# BJ_GIRA_Taster4_4.net
KiCad netlist of a schematic drawn in EAGLE
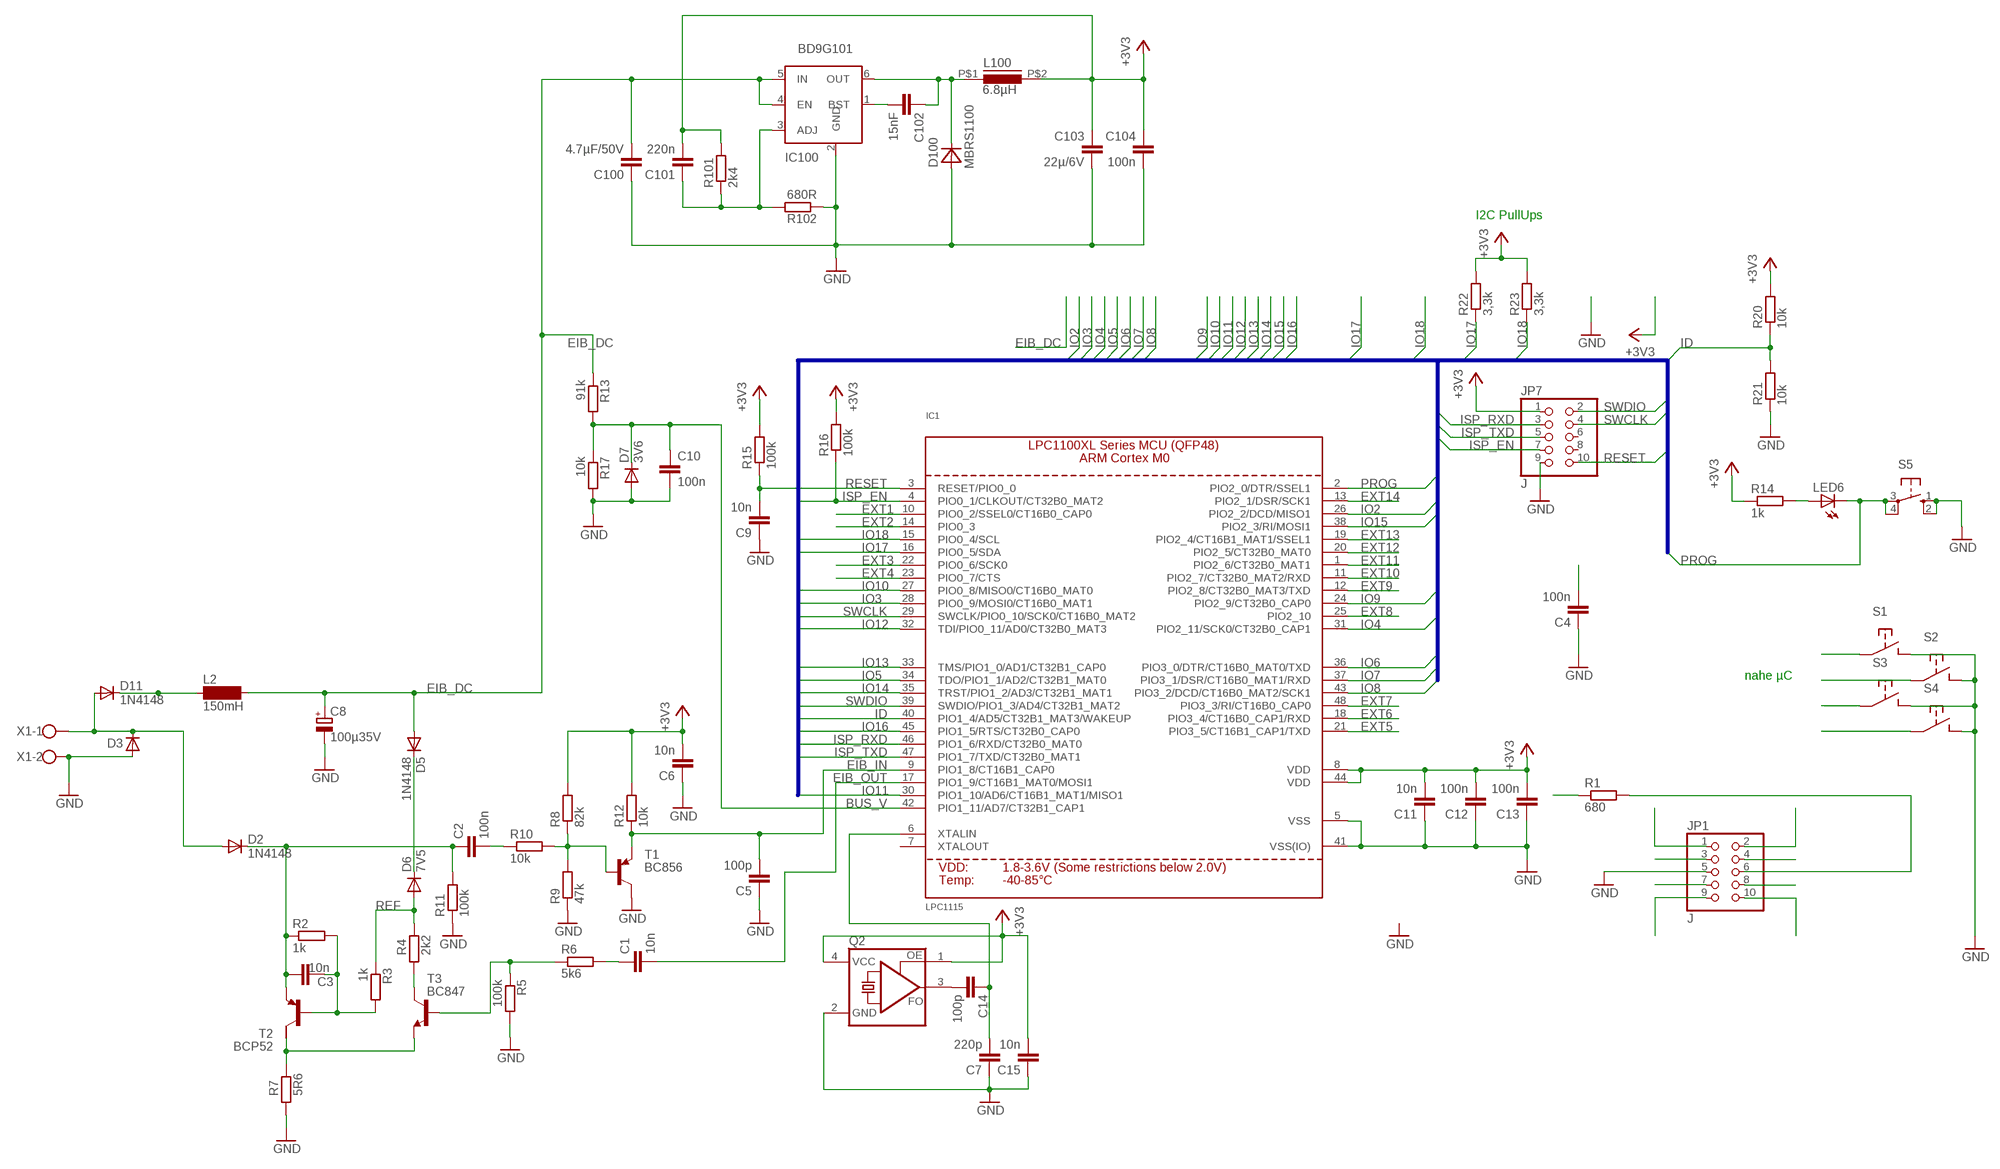
[diagram p0: schematic, sheet 1]

(export (version "E")
  (design (tool "Eeschema 10.0.6"))
  (components
    (comp (ref "C1")
      (value "10n")
      (footprint "eagle-import:C1206")
      (libsource (lib "eagle-import") (part "C-EUC1206"))
    )
    (comp (ref "C2")
      (value "100n")
      (footprint "eagle-import:C1206")
      (libsource (lib "eagle-import") (part "C-EUC1206"))
    )
    (comp (ref "C3")
      (value "10n")
      (footprint "eagle-import:C1206")
      (libsource (lib "eagle-import") (part "C-EUC1206"))
    )
    (comp (ref "C4")
      (value "100n")
      (footprint "eagle-import:C1206")
      (libsource (lib "eagle-import") (part "C-EUC1206"))
    )
    (comp (ref "C5")
      (value "100p")
      (footprint "eagle-import:C1206")
      (libsource (lib "eagle-import") (part "C-EUC1206"))
    )
    (comp (ref "C6")
      (value "10n")
      (footprint "eagle-import:C1206")
      (libsource (lib "eagle-import") (part "C-EUC1206"))
    )
    (comp (ref "C7")
      (value "220p")
      (footprint "eagle-import:C1206")
      (libsource (lib "eagle-import") (part "C-EUC1206"))
    )
    (comp (ref "C8")
      (value "100µ35V")
      (footprint "eagle-import:E3,5-8")
      (libsource (lib "eagle-import") (part "CPOL-EUE3.5-8"))
    )
    (comp (ref "C9")
      (value "10n")
      (footprint "eagle-import:C1206")
      (libsource (lib "eagle-import") (part "C-EUC1206"))
    )
    (comp (ref "C10")
      (value "100n")
      (footprint "eagle-import:C1206")
      (libsource (lib "eagle-import") (part "C-EUC1206"))
    )
    (comp (ref "C11")
      (value "10n")
      (footprint "eagle-import:C1206")
      (libsource (lib "eagle-import") (part "C-EUC1206"))
    )
    (comp (ref "C12")
      (value "100n")
      (footprint "eagle-import:C1206")
      (libsource (lib "eagle-import") (part "C-EUC1206"))
    )
    (comp (ref "C13")
      (value "100n")
      (footprint "eagle-import:C1206")
      (libsource (lib "eagle-import") (part "C-EUC1206"))
    )
    (comp (ref "C14")
      (value "100p")
      (footprint "eagle-import:C1206")
      (libsource (lib "eagle-import") (part "C-EUC1206"))
    )
    (comp (ref "C15")
      (value "10n")
      (footprint "eagle-import:C1206")
      (libsource (lib "eagle-import") (part "C-EUC1206"))
    )
    (comp (ref "C100")
      (value "4.7µF/50V")
      (footprint "eagle-import:C1206")
      (libsource (lib "eagle-import") (part "C-EUC1206"))
    )
    (comp (ref "C101")
      (value "220n")
      (footprint "eagle-import:C1206")
      (libsource (lib "eagle-import") (part "C-EUC1206"))
    )
    (comp (ref "C102")
      (value "15nF")
      (footprint "eagle-import:C1206")
      (libsource (lib "eagle-import") (part "C-EUC1206"))
    )
    (comp (ref "C103")
      (value "22µ/6V")
      (footprint "eagle-import:C1206")
      (libsource (lib "eagle-import") (part "C-EUC1206"))
    )
    (comp (ref "C104")
      (value "100n")
      (footprint "eagle-import:C1206")
      (libsource (lib "eagle-import") (part "C-EUC1206"))
    )
    (comp (ref "D2")
      (value "1N4148")
      (footprint "eagle-import:MINIMELF")
      (libsource (lib "eagle-import") (part "DIODE-MINIMELF"))
    )
    (comp (ref "D3")
      (value "D-SMB")
      (footprint "eagle-import:SMB")
      (libsource (lib "eagle-import") (part "D-SMB"))
    )
    (comp (ref "D5")
      (value "1N4148")
      (footprint "eagle-import:MINIMELF")
      (libsource (lib "eagle-import") (part "DIODE-MINIMELF"))
    )
    (comp (ref "D6")
      (value "7V5")
      (footprint "eagle-import:MINIMELF")
      (libsource (lib "eagle-import") (part "DIODE-MINIMELF"))
    )
    (comp (ref "D7")
      (value "3V6")
      (footprint "eagle-import:MINIMELF")
      (libsource (lib "eagle-import") (part "DIODE-MINIMELF"))
    )
    (comp (ref "D11")
      (value "1N4148")
      (footprint "eagle-import:MINIMELF")
      (libsource (lib "eagle-import") (part "DIODE-MINIMELF"))
    )
    (comp (ref "D100")
      (value "MBRS1100")
      (footprint "eagle-import:SMA")
      (libsource (lib "eagle-import") (part "MBRA340T3"))
    )
    (comp (ref "IC1")
      (value "LPC1115")
      (footprint "eagle-import:LQFP48")
      (libsource (lib "eagle-import") (part "LPC1113/4/5_QFP48_XLSERIES"))
    )
    (comp (ref "IC100")
      (value "BD9G101")
      (footprint "eagle-import:SOT23-6")
      (libsource (lib "eagle-import") (part "BD9G101GBD9G101G-SOT23-6"))
    )
    (comp (ref "JP1")
      (value "J")
      (footprint "eagle-import:2X05M")
      (libsource (lib "eagle-import") (part "PINHD-2X05_2.00"))
    )
    (comp (ref "JP7")
      (value "J")
      (footprint "eagle-import:2X05M")
      (libsource (lib "eagle-import") (part "PINHD-2X05_2.00"))
    )
    (comp (ref "L2")
      (value "150mH")
      (footprint "eagle-import:BS11")
      (libsource (lib "eagle-import") (part "BS11"))
    )
    (comp (ref "L100")
      (value "6.8µH")
      (footprint "eagle-import:PIS2812")
      (libsource (lib "eagle-import") (part "IND_FASTRON_1616FPS"))
    )
    (comp (ref "LED6")
      (value "LED3MM")
      (footprint "eagle-import:LED3MM")
      (libsource (lib "eagle-import") (part "LED3MM"))
    )
    (comp (ref "Q2")
      (value "ASFL")
      (footprint "eagle-import:ASF")
      (libsource (lib "eagle-import") (part "ASFL"))
    )
    (comp (ref "R1")
      (value "680")
      (footprint "eagle-import:R1206")
      (libsource (lib "eagle-import") (part "R-EU_R1206"))
    )
    (comp (ref "R2")
      (value "1k")
      (footprint "eagle-import:R1206")
      (libsource (lib "eagle-import") (part "R-EU_R1206"))
    )
    (comp (ref "R3")
      (value "1k")
      (footprint "eagle-import:R1206")
      (libsource (lib "eagle-import") (part "R-EU_R1206"))
    )
    (comp (ref "R4")
      (value "2k2")
      (footprint "eagle-import:R1206")
      (libsource (lib "eagle-import") (part "R-EU_R1206"))
    )
    (comp (ref "R5")
      (value "100k")
      (footprint "eagle-import:R1206")
      (libsource (lib "eagle-import") (part "R-EU_R1206"))
    )
    (comp (ref "R6")
      (value "5k6")
      (footprint "eagle-import:R1206")
      (libsource (lib "eagle-import") (part "R-EU_R1206"))
    )
    (comp (ref "R7")
      (value "5R6")
      (footprint "eagle-import:R1206")
      (libsource (lib "eagle-import") (part "R-EU_R1206"))
    )
    (comp (ref "R8")
      (value "82k")
      (footprint "eagle-import:R1206")
      (libsource (lib "eagle-import") (part "R-EU_R1206"))
    )
    (comp (ref "R9")
      (value "47k")
      (footprint "eagle-import:R1206")
      (libsource (lib "eagle-import") (part "R-EU_R1206"))
    )
    (comp (ref "R10")
      (value "10k")
      (footprint "eagle-import:R1206")
      (libsource (lib "eagle-import") (part "R-EU_R1206"))
    )
    (comp (ref "R11")
      (value "100k")
      (footprint "eagle-import:R1206")
      (libsource (lib "eagle-import") (part "R-EU_R1206"))
    )
    (comp (ref "R12")
      (value "10k")
      (footprint "eagle-import:R1206")
      (libsource (lib "eagle-import") (part "R-EU_R1206"))
    )
    (comp (ref "R13")
      (value "91k")
      (footprint "eagle-import:R1206")
      (libsource (lib "eagle-import") (part "R-EU_R1206"))
    )
    (comp (ref "R14")
      (value "1k")
      (footprint "eagle-import:R1206")
      (libsource (lib "eagle-import") (part "R-EU_R1206"))
    )
    (comp (ref "R15")
      (value "100k")
      (footprint "eagle-import:R1206")
      (libsource (lib "eagle-import") (part "R-EU_R1206"))
    )
    (comp (ref "R16")
      (value "100k")
      (footprint "eagle-import:R1206")
      (libsource (lib "eagle-import") (part "R-EU_R1206"))
    )
    (comp (ref "R17")
      (value "10k")
      (footprint "eagle-import:R1206")
      (libsource (lib "eagle-import") (part "R-EU_R1206"))
    )
    (comp (ref "R20")
      (value "10k")
      (footprint "eagle-import:R1206")
      (libsource (lib "eagle-import") (part "R-EU_R1206"))
    )
    (comp (ref "R21")
      (value "10k")
      (footprint "eagle-import:R1206")
      (libsource (lib "eagle-import") (part "R-EU_R1206"))
    )
    (comp (ref "R22")
      (value "3,3k")
      (footprint "eagle-import:R1206")
      (libsource (lib "eagle-import") (part "R-EU_R1206"))
    )
    (comp (ref "R23")
      (value "3,3k")
      (footprint "eagle-import:R1206")
      (libsource (lib "eagle-import") (part "R-EU_R1206"))
    )
    (comp (ref "R101")
      (value "2k4")
      (footprint "eagle-import:R1206")
      (libsource (lib "eagle-import") (part "R-EU_R1206"))
    )
    (comp (ref "R102")
      (value "680R")
      (footprint "eagle-import:R1206")
      (libsource (lib "eagle-import") (part "R-EU_R1206"))
    )
    (comp (ref "S1")
      (value "33053305A")
      (footprint "eagle-import:3305A")
      (libsource (lib "eagle-import") (part "33053305A"))
    )
    (comp (ref "S2")
      (value "33053305A")
      (footprint "eagle-import:3305A")
      (libsource (lib "eagle-import") (part "33053305A"))
    )
    (comp (ref "S3")
      (value "33053305A")
      (footprint "eagle-import:3305A")
      (libsource (lib "eagle-import") (part "33053305A"))
    )
    (comp (ref "S4")
      (value "33053305A")
      (footprint "eagle-import:3305A")
      (libsource (lib "eagle-import") (part "33053305A"))
    )
    (comp (ref "S5")
      (value "10-XX")
      (footprint "eagle-import:B3F-10XX")
      (libsource (lib "eagle-import") (part "10-XX"))
    )
    (comp (ref "T1")
      (value "BC856")
      (footprint "eagle-import:SOT23-BEC")
      (libsource (lib "eagle-import") (part "BC856SMDB"))
    )
    (comp (ref "T2")
      (value "BCP52")
      (footprint "eagle-import:SOT223")
      (libsource (lib "eagle-import") (part "FZT753SMD"))
    )
    (comp (ref "T3")
      (value "BC847")
      (footprint "eagle-import:SOT23")
      (libsource (lib "eagle-import") (part "BC847"))
    )
    (comp (ref "X1")
      (value "W237-02P")
      (footprint "eagle-import:W237-132")
      (libsource (lib "eagle-import") (part "W237-02P"))
    )
  )
  (nets
    (net (code "1") (name "+3V3") (class "Default")
      (node (ref "C101") (pin "2") (pinfunction "2_2") (pintype "passive"))
      (node (ref "C103") (pin "1") (pinfunction "1_1") (pintype "passive"))
      (node (ref "C104") (pin "1") (pinfunction "1_1") (pintype "passive"))
      (node (ref "C11") (pin "2") (pinfunction "2_2") (pintype "passive"))
      (node (ref "C12") (pin "2") (pinfunction "2_2") (pintype "passive"))
      (node (ref "C13") (pin "2") (pinfunction "2_2") (pintype "passive"))
      (node (ref "C15") (pin "2") (pinfunction "2_2") (pintype "passive"))
      (node (ref "C6") (pin "2") (pinfunction "2_2") (pintype "passive"))
      (node (ref "IC1") (pin "44") (pinfunction "VDD_44") (pintype "power_in"))
      (node (ref "IC1") (pin "8") (pinfunction "VDD_8") (pintype "power_in"))
      (node (ref "JP1") (pin "4") (pinfunction "4_4") (pintype "passive"))
      (node (ref "JP7") (pin "1") (pinfunction "1_1") (pintype "passive"))
      (node (ref "L100") (pin "P$2") (pinfunction "2_P$2") (pintype "passive"))
      (node (ref "Q2") (pin "1") (pinfunction "OE_1") (pintype "input"))
      (node (ref "Q2") (pin "4") (pinfunction "VCC_4") (pintype "power_in"))
      (node (ref "R101") (pin "2") (pinfunction "2_2") (pintype "passive"))
      (node (ref "R12") (pin "2") (pinfunction "2_2") (pintype "passive"))
      (node (ref "R14") (pin "1") (pinfunction "1_1") (pintype "passive"))
      (node (ref "R15") (pin "2") (pinfunction "2_2") (pintype "passive"))
      (node (ref "R16") (pin "2") (pinfunction "2_2") (pintype "passive"))
      (node (ref "R20") (pin "2") (pinfunction "2_2") (pintype "passive"))
      (node (ref "R22") (pin "2") (pinfunction "2_2") (pintype "passive"))
      (node (ref "R23") (pin "2") (pinfunction "2_2") (pintype "passive"))
      (node (ref "R8") (pin "2") (pinfunction "2_2") (pintype "passive"))
    )
    (net (code "2") (name "/BUS_V") (class "Default")
      (node (ref "C10") (pin "2") (pinfunction "2_2") (pintype "passive"))
      (node (ref "D7") (pin "C") (pinfunction "C_C") (pintype "passive"))
      (node (ref "IC1") (pin "42") (pinfunction "PIO1_11/AD7/CT32B1_CAP1_42") (pintype "bidirectional"))
      (node (ref "R13") (pin "2") (pinfunction "2_2") (pintype "passive"))
      (node (ref "R17") (pin "1") (pinfunction "1_1") (pintype "passive"))
    )
    (net (code "3") (name "/EIB_DC") (class "Default")
      (node (ref "C100") (pin "2") (pinfunction "2_2") (pintype "passive"))
      (node (ref "C8") (pin "+") (pinfunction "+_+") (pintype "passive"))
      (node (ref "D5") (pin "A") (pinfunction "A_A") (pintype "passive"))
      (node (ref "IC100") (pin "4") (pinfunction "EN_4") (pintype "input"))
      (node (ref "IC100") (pin "5") (pinfunction "IN_5") (pintype "input"))
      (node (ref "L2") (pin "2") (pinfunction "2_2") (pintype "passive"))
      (node (ref "R13") (pin "1") (pinfunction "1_1") (pintype "passive"))
    )
    (net (code "4") (name "/EIB_IN") (class "Default")
      (node (ref "C5") (pin "2") (pinfunction "2_2") (pintype "passive"))
      (node (ref "IC1") (pin "9") (pinfunction "PIO1_8/CT16B1_CAP0_9") (pintype "bidirectional"))
      (node (ref "R12") (pin "1") (pinfunction "1_1") (pintype "passive"))
      (node (ref "T1") (pin "E") (pinfunction "E_E") (pintype "passive"))
    )
    (net (code "5") (name "/EIB_OUT") (class "Default")
      (node (ref "C1") (pin "2") (pinfunction "2_2") (pintype "passive"))
      (node (ref "IC1") (pin "17") (pinfunction "PIO1_9/CT16B1_MAT0/MOSI1_17") (pintype "bidirectional"))
    )
    (net (code "6") (name "/EXT1") (class "Default")
      (node (ref "IC1") (pin "10") (pinfunction "PIO0_2/SSEL0/CT16B0_CAP0_10") (pintype "bidirectional"))
    )
    (net (code "7") (name "/EXT2") (class "Default")
      (node (ref "IC1") (pin "14") (pinfunction "PIO0_3_14") (pintype "bidirectional"))
    )
    (net (code "8") (name "/EXT3") (class "Default")
      (node (ref "IC1") (pin "22") (pinfunction "PIO0_6/SCK0_22") (pintype "bidirectional"))
    )
    (net (code "9") (name "/EXT4") (class "Default")
      (node (ref "IC1") (pin "23") (pinfunction "PIO0_7/CTS_23") (pintype "bidirectional"))
      (node (ref "S2") (pin "P$1") (pinfunction "1_P$1") (pintype "bidirectional"))
    )
    (net (code "10") (name "/EXT5") (class "Default")
      (node (ref "IC1") (pin "21") (pinfunction "PIO3_5/CT16B1_CAP1/TXD_21") (pintype "bidirectional"))
      (node (ref "JP1") (pin "7") (pinfunction "7_7") (pintype "passive"))
    )
    (net (code "11") (name "/EXT6") (class "Default")
      (node (ref "IC1") (pin "18") (pinfunction "PIO3_4/CT16B0_CAP1/RXD_18") (pintype "bidirectional"))
      (node (ref "JP1") (pin "8") (pinfunction "8_8") (pintype "passive"))
    )
    (net (code "12") (name "/EXT7") (class "Default")
      (node (ref "IC1") (pin "48") (pinfunction "PIO3_3/RI/CT16B0_CAP0_48") (pintype "bidirectional"))
      (node (ref "S1") (pin "P$1") (pinfunction "1_P$1") (pintype "bidirectional"))
    )
    (net (code "13") (name "/EXT8") (class "Default")
      (node (ref "IC1") (pin "25") (pinfunction "PIO2_10_25") (pintype "bidirectional"))
      (node (ref "S3") (pin "P$1") (pinfunction "1_P$1") (pintype "bidirectional"))
    )
    (net (code "14") (name "/EXT9") (class "Default")
      (node (ref "IC1") (pin "12") (pinfunction "PIO2_8/CT32B0_MAT3/TXD_12") (pintype "bidirectional"))
    )
    (net (code "15") (name "/EXT10") (class "Default")
      (node (ref "IC1") (pin "11") (pinfunction "PIO2_7/CT32B0_MAT2/RXD_11") (pintype "bidirectional"))
    )
    (net (code "16") (name "/EXT11") (class "Default")
      (node (ref "IC1") (pin "1") (pinfunction "PIO2_6/CT32B0_MAT1_1") (pintype "bidirectional"))
      (node (ref "JP1") (pin "10") (pinfunction "10_10") (pintype "passive"))
      (node (ref "R1") (pin "1") (pinfunction "1_1") (pintype "passive"))
    )
    (net (code "17") (name "/EXT12") (class "Default")
      (node (ref "IC1") (pin "20") (pinfunction "PIO2_5/CT32B0_MAT0_20") (pintype "bidirectional"))
    )
    (net (code "18") (name "/EXT13") (class "Default")
      (node (ref "IC1") (pin "19") (pinfunction "PIO2_4/CT16B1_MAT1/SSEL1_19") (pintype "bidirectional"))
    )
    (net (code "19") (name "/EXT14") (class "Default")
      (node (ref "IC1") (pin "13") (pinfunction "PIO2_1/DSR/SCK1_13") (pintype "bidirectional"))
      (node (ref "JP1") (pin "1") (pinfunction "1_1") (pintype "passive"))
    )
    (net (code "20") (name "/ID") (class "Default")
      (node (ref "IC1") (pin "40") (pinfunction "PIO1_4/AD5/CT32B1_MAT3/WAKEUP_40") (pintype "bidirectional"))
      (node (ref "R20") (pin "1") (pinfunction "1_1") (pintype "passive"))
      (node (ref "R21") (pin "2") (pinfunction "2_2") (pintype "passive"))
    )
    (net (code "21") (name "/IO2") (class "Default")
      (node (ref "IC1") (pin "26") (pinfunction "PIO2_2/DCD/MISO1_26") (pintype "bidirectional"))
      (node (ref "JP1") (pin "2") (pinfunction "2_2") (pintype "passive"))
    )
    (net (code "22") (name "/IO3") (class "Default")
      (node (ref "IC1") (pin "28") (pinfunction "PIO0_9/MOSI0/CT16B0_MAT1_28") (pintype "bidirectional"))
    )
    (net (code "23") (name "/IO4") (class "Default")
      (node (ref "IC1") (pin "31") (pinfunction "PIO2_11/SCK0/CT32B0_CAP1_31") (pintype "bidirectional"))
      (node (ref "JP1") (pin "3") (pinfunction "3_3") (pintype "passive"))
    )
    (net (code "24") (name "/IO5") (class "Default")
      (node (ref "IC1") (pin "34") (pinfunction "TDO/PIO1_1/AD2/CT32B1_MAT0_34") (pintype "bidirectional"))
    )
    (net (code "25") (name "/IO6") (class "Default")
      (node (ref "IC1") (pin "36") (pinfunction "PIO3_0/DTR/CT16B0_MAT0/TXD_36") (pintype "bidirectional"))
    )
    (net (code "26") (name "/IO7") (class "Default")
      (node (ref "IC1") (pin "37") (pinfunction "PIO3_1/DSR/CT16B0_MAT1/RXD_37") (pintype "bidirectional"))
    )
    (net (code "27") (name "/IO8") (class "Default")
      (node (ref "IC1") (pin "43") (pinfunction "PIO3_2/DCD/CT16B0_MAT2/SCK1_43") (pintype "bidirectional"))
    )
    (net (code "28") (name "/IO9") (class "Default")
      (node (ref "IC1") (pin "24") (pinfunction "PIO2_9/CT32B0_CAP0_24") (pintype "bidirectional"))
      (node (ref "S4") (pin "P$1") (pinfunction "1_P$1") (pintype "bidirectional"))
    )
    (net (code "29") (name "/IO10") (class "Default")
      (node (ref "IC1") (pin "27") (pinfunction "PIO0_8/MISO0/CT16B0_MAT0_27") (pintype "bidirectional"))
    )
    (net (code "30") (name "/IO11") (class "Default")
      (node (ref "IC1") (pin "30") (pinfunction "PIO1_10/AD6/CT16B1_MAT1/MISO1_30") (pintype "bidirectional"))
    )
    (net (code "31") (name "/IO12") (class "Default")
      (node (ref "IC1") (pin "32") (pinfunction "TDI/PIO0_11/AD0/CT32B0_MAT3_32") (pintype "bidirectional"))
    )
    (net (code "32") (name "/IO13") (class "Default")
      (node (ref "IC1") (pin "33") (pinfunction "TMS/PIO1_0/AD1/CT32B1_CAP0_33") (pintype "bidirectional"))
    )
    (net (code "33") (name "/IO14") (class "Default")
      (node (ref "IC1") (pin "35") (pinfunction "TRST/PIO1_2/AD3/CT32B1_MAT1_35") (pintype "bidirectional"))
    )
    (net (code "34") (name "/IO15") (class "Default")
      (node (ref "IC1") (pin "38") (pinfunction "PIO2_3/RI/MOSI1_38") (pintype "bidirectional"))
      (node (ref "JP1") (pin "9") (pinfunction "9_9") (pintype "passive"))
    )
    (net (code "35") (name "/IO16") (class "Default")
      (node (ref "IC1") (pin "45") (pinfunction "PIO1_5/RTS/CT32B0_CAP0_45") (pintype "bidirectional"))
    )
    (net (code "36") (name "/IO17") (class "Default")
      (node (ref "IC1") (pin "16") (pinfunction "PIO0_5/SDA_16") (pintype "bidirectional"))
      (node (ref "R22") (pin "1") (pinfunction "1_1") (pintype "passive"))
    )
    (net (code "37") (name "/IO18") (class "Default")
      (node (ref "IC1") (pin "15") (pinfunction "PIO0_4/SCL_15") (pintype "bidirectional"))
      (node (ref "R23") (pin "1") (pinfunction "1_1") (pintype "passive"))
    )
    (net (code "38") (name "/ISP_EN") (class "Default")
      (node (ref "IC1") (pin "4") (pinfunction "PIO0_1/CLKOUT/CT32B0_MAT2_4") (pintype "bidirectional"))
      (node (ref "JP7") (pin "7") (pinfunction "7_7") (pintype "passive"))
      (node (ref "R16") (pin "1") (pinfunction "1_1") (pintype "passive"))
    )
    (net (code "39") (name "/ISP_RXD") (class "Default")
      (node (ref "IC1") (pin "46") (pinfunction "PIO1_6/RXD/CT32B0_MAT0_46") (pintype "bidirectional"))
      (node (ref "JP7") (pin "3") (pinfunction "3_3") (pintype "passive"))
    )
    (net (code "40") (name "/ISP_TXD") (class "Default")
      (node (ref "IC1") (pin "47") (pinfunction "PIO1_7/TXD/CT32B0_MAT1_47") (pintype "bidirectional"))
      (node (ref "JP7") (pin "5") (pinfunction "5_5") (pintype "passive"))
    )
    (net (code "41") (name "/PROG") (class "Default")
      (node (ref "IC1") (pin "2") (pinfunction "PIO2_0/DTR/SSEL1_2") (pintype "bidirectional"))
      (node (ref "LED6") (pin "K") (pinfunction "C_K") (pintype "passive"))
      (node (ref "S5") (pin "3") (pinfunction "P_3") (pintype "passive"))
      (node (ref "S5") (pin "4") (pinfunction "P1_4") (pintype "passive"))
    )
    (net (code "42") (name "/REF") (class "Default")
      (node (ref "D6") (pin "A") (pinfunction "A_A") (pintype "passive"))
      (node (ref "R3") (pin "1") (pinfunction "1_1") (pintype "passive"))
      (node (ref "R4") (pin "2") (pinfunction "2_2") (pintype "passive"))
    )
    (net (code "43") (name "/RESET") (class "Default")
      (node (ref "C9") (pin "2") (pinfunction "2_2") (pintype "passive"))
      (node (ref "IC1") (pin "3") (pinfunction "RESET/PIO0_0_3") (pintype "bidirectional"))
      (node (ref "JP7") (pin "10") (pinfunction "10_10") (pintype "passive"))
      (node (ref "R15") (pin "1") (pinfunction "1_1") (pintype "passive"))
    )
    (net (code "44") (name "/SWCLK") (class "Default")
      (node (ref "IC1") (pin "29") (pinfunction "SWCLK/PIO0_10/SCK0/CT16B0_MAT2_29") (pintype "bidirectional"))
      (node (ref "JP7") (pin "4") (pinfunction "4_4") (pintype "passive"))
    )
    (net (code "45") (name "/SWDIO") (class "Default")
      (node (ref "IC1") (pin "39") (pinfunction "SWDIO/PIO1_3/AD4/CT32B1_MAT2_39") (pintype "bidirectional"))
      (node (ref "JP7") (pin "2") (pinfunction "2_2") (pintype "passive"))
    )
    (net (code "46") (name "GND") (class "Default")
      (node (ref "C10") (pin "1") (pinfunction "1_1") (pintype "passive"))
      (node (ref "C100") (pin "1") (pinfunction "1_1") (pintype "passive"))
      (node (ref "C103") (pin "2") (pinfunction "2_2") (pintype "passive"))
      (node (ref "C104") (pin "2") (pinfunction "2_2") (pintype "passive"))
      (node (ref "C11") (pin "1") (pinfunction "1_1") (pintype "passive"))
      (node (ref "C12") (pin "1") (pinfunction "1_1") (pintype "passive"))
      (node (ref "C13") (pin "1") (pinfunction "1_1") (pintype "passive"))
      (node (ref "C15") (pin "1") (pinfunction "1_1") (pintype "passive"))
      (node (ref "C4") (pin "1") (pinfunction "1_1") (pintype "passive"))
      (node (ref "C5") (pin "1") (pinfunction "1_1") (pintype "passive"))
      (node (ref "C6") (pin "1") (pinfunction "1_1") (pintype "passive"))
      (node (ref "C7") (pin "1") (pinfunction "1_1") (pintype "passive"))
      (node (ref "C8") (pin "-") (pinfunction "-_-") (pintype "passive"))
      (node (ref "C9") (pin "1") (pinfunction "1_1") (pintype "passive"))
      (node (ref "D100") (pin "A") (pinfunction "A_A") (pintype "passive"))
      (node (ref "D3") (pin "2") (pinfunction "A_2") (pintype "passive"))
      (node (ref "D7") (pin "A") (pinfunction "A_A") (pintype "passive"))
      (node (ref "IC1") (pin "41") (pinfunction "VSS(IO)_41") (pintype "power_in"))
      (node (ref "IC1") (pin "5") (pinfunction "VSS_5") (pintype "power_in"))
      (node (ref "IC100") (pin "2") (pinfunction "GND_2") (pintype "power_in"))
      (node (ref "JP1") (pin "5") (pinfunction "5_5") (pintype "passive"))
      (node (ref "JP7") (pin "9") (pinfunction "9_9") (pintype "passive"))
      (node (ref "Q2") (pin "2") (pinfunction "GND_2") (pintype "power_in"))
      (node (ref "R102") (pin "1") (pinfunction "1_1") (pintype "passive"))
      (node (ref "R11") (pin "1") (pinfunction "1_1") (pintype "passive"))
      (node (ref "R17") (pin "2") (pinfunction "2_2") (pintype "passive"))
      (node (ref "R21") (pin "1") (pinfunction "1_1") (pintype "passive"))
      (node (ref "R5") (pin "2") (pinfunction "2_2") (pintype "passive"))
      (node (ref "R7") (pin "1") (pinfunction "1_1") (pintype "passive"))
      (node (ref "R9") (pin "1") (pinfunction "1_1") (pintype "passive"))
      (node (ref "S1") (pin "P$2") (pinfunction "2_P$2") (pintype "bidirectional"))
      (node (ref "S2") (pin "P$2") (pinfunction "2_P$2") (pintype "bidirectional"))
      (node (ref "S3") (pin "P$2") (pinfunction "2_P$2") (pintype "bidirectional"))
      (node (ref "S4") (pin "P$2") (pinfunction "2_P$2") (pintype "bidirectional"))
      (node (ref "S5") (pin "1") (pinfunction "S_1") (pintype "passive"))
      (node (ref "S5") (pin "2") (pinfunction "S1_2") (pintype "passive"))
      (node (ref "T1") (pin "C") (pinfunction "C_C") (pintype "passive"))
      (node (ref "X1") (pin "2") (pinfunction "KL_2") (pintype "passive"))
    )
    (net (code "47") (name "Net-(C1-Pad1)") (class "Default")
      (node (ref "C1") (pin "1") (pinfunction "1_1") (pintype "passive"))
      (node (ref "R6") (pin "2") (pinfunction "2_2") (pintype "passive"))
    )
    (net (code "48") (name "Net-(C2-Pad2)") (class "Default")
      (node (ref "C2") (pin "2") (pinfunction "2_2") (pintype "passive"))
      (node (ref "R10") (pin "1") (pinfunction "1_1") (pintype "passive"))
    )
    (net (code "49") (name "Net-(D3-C)") (class "Default")
      (node (ref "D11") (pin "A") (pinfunction "A_A") (pintype "passive"))
      (node (ref "D2") (pin "A") (pinfunction "A_A") (pintype "passive"))
      (node (ref "D3") (pin "1") (pinfunction "C_1") (pintype "passive"))
      (node (ref "X1") (pin "1") (pinfunction "KL_1") (pintype "passive"))
    )
    (net (code "50") (name "Net-(D5-PadC)") (class "Default")
      (node (ref "D5") (pin "C") (pinfunction "C_C") (pintype "passive"))
      (node (ref "D6") (pin "C") (pinfunction "C_C") (pintype "passive"))
    )
    (net (code "51") (name "Net-(D11-PadC)") (class "Default")
      (node (ref "D11") (pin "C") (pinfunction "C_C") (pintype "passive"))
      (node (ref "L2") (pin "1") (pinfunction "1_1") (pintype "passive"))
    )
    (net (code "52") (name "Net-(IC1-XTALIN)") (class "Default")
      (node (ref "C14") (pin "1") (pinfunction "1_1") (pintype "passive"))
      (node (ref "C7") (pin "2") (pinfunction "2_2") (pintype "passive"))
      (node (ref "IC1") (pin "6") (pinfunction "XTALIN_6") (pintype "input"))
    )
    (net (code "53") (name "Net-(IC100-ADJ)") (class "Default")
      (node (ref "C101") (pin "1") (pinfunction "1_1") (pintype "passive"))
      (node (ref "IC100") (pin "3") (pinfunction "ADJ_3") (pintype "passive"))
      (node (ref "R101") (pin "1") (pinfunction "1_1") (pintype "passive"))
      (node (ref "R102") (pin "2") (pinfunction "2_2") (pintype "passive"))
    )
    (net (code "54") (name "Net-(IC100-BST)") (class "Default")
      (node (ref "C102") (pin "2") (pinfunction "2_2") (pintype "passive"))
      (node (ref "IC100") (pin "1") (pinfunction "BST_1") (pintype "output"))
    )
    (net (code "55") (name "Net-(IC100-OUT)") (class "Default")
      (node (ref "C102") (pin "1") (pinfunction "1_1") (pintype "passive"))
      (node (ref "D100") (pin "C") (pinfunction "C_C") (pintype "passive"))
      (node (ref "IC100") (pin "6") (pinfunction "OUT_6") (pintype "output"))
      (node (ref "L100") (pin "P$1") (pinfunction "1_P$1") (pintype "passive"))
    )
    (net (code "56") (name "Net-(JP1-Pad6)") (class "Default")
      (node (ref "JP1") (pin "6") (pinfunction "6_6") (pintype "passive"))
      (node (ref "R1") (pin "2") (pinfunction "2_2") (pintype "passive"))
    )
    (net (code "57") (name "Net-(LED6-PadA)") (class "Default")
      (node (ref "LED6") (pin "A") (pinfunction "A_A") (pintype "passive"))
      (node (ref "R14") (pin "2") (pinfunction "2_2") (pintype "passive"))
    )
    (net (code "58") (name "Net-(Q2-FO)") (class "Default")
      (node (ref "C14") (pin "2") (pinfunction "2_2") (pintype "passive"))
      (node (ref "Q2") (pin "3") (pinfunction "FO_3") (pintype "output"))
    )
    (net (code "59") (name "Net-(R10-Pad2)") (class "Default")
      (node (ref "R10") (pin "2") (pinfunction "2_2") (pintype "passive"))
      (node (ref "R8") (pin "1") (pinfunction "1_1") (pintype "passive"))
      (node (ref "R9") (pin "2") (pinfunction "2_2") (pintype "passive"))
      (node (ref "T1") (pin "B") (pinfunction "B_B") (pintype "passive"))
    )
    (net (code "60") (name "Net-(T2-B)") (class "Default")
      (node (ref "C3") (pin "2") (pinfunction "2_2") (pintype "passive"))
      (node (ref "R2") (pin "2") (pinfunction "2_2") (pintype "passive"))
      (node (ref "R3") (pin "2") (pinfunction "2_2") (pintype "passive"))
      (node (ref "T2") (pin "1") (pinfunction "B_1") (pintype "passive"))
    )
    (net (code "61") (name "Net-(T2-C)") (class "Default")
      (node (ref "R7") (pin "2") (pinfunction "2_2") (pintype "passive"))
      (node (ref "T2") (pin "2") (pinfunction "C_2") (pintype "passive"))
      (node (ref "T3") (pin "2") (pinfunction "E_2") (pintype "passive"))
    )
    (net (code "62") (name "Net-(T2-E)") (class "Default")
      (node (ref "C2") (pin "1") (pinfunction "1_1") (pintype "passive"))
      (node (ref "C3") (pin "1") (pinfunction "1_1") (pintype "passive"))
      (node (ref "D2") (pin "C") (pinfunction "C_C") (pintype "passive"))
      (node (ref "R11") (pin "2") (pinfunction "2_2") (pintype "passive"))
      (node (ref "R2") (pin "1") (pinfunction "1_1") (pintype "passive"))
      (node (ref "T2") (pin "3") (pinfunction "E_3") (pintype "passive"))
    )
    (net (code "63") (name "Net-(T3-B)") (class "Default")
      (node (ref "R5") (pin "1") (pinfunction "1_1") (pintype "passive"))
      (node (ref "R6") (pin "1") (pinfunction "1_1") (pintype "passive"))
      (node (ref "T3") (pin "1") (pinfunction "B_1") (pintype "passive"))
    )
    (net (code "64") (name "Net-(T3-C)") (class "Default")
      (node (ref "R4") (pin "1") (pinfunction "1_1") (pintype "passive"))
      (node (ref "T3") (pin "3") (pinfunction "C_3") (pintype "passive"))
    )
    (net (code "65") (name "unconnected-(C4-Pad2)") (class "Default")
      (node (ref "C4") (pin "2") (pinfunction "2_2") (pintype "passive"))
    )
    (net (code "66") (name "unconnected-(IC1-XTALOUT-Pad7)") (class "Default")
      (node (ref "IC1") (pin "7") (pinfunction "XTALOUT_7") (pintype "output"))
    )
    (net (code "67") (name "unconnected-(JP7-Pad6)") (class "Default")
      (node (ref "JP7") (pin "6") (pinfunction "6_6") (pintype "passive"))
    )
    (net (code "68") (name "unconnected-(JP7-Pad8)") (class "Default")
      (node (ref "JP7") (pin "8") (pinfunction "8_8") (pintype "passive"))
    )
    (net (code "69") (name "unconnected-(T2-C{slash}-Pad4)") (class "Default")
      (node (ref "T2") (pin "4") (pinfunction "C/_4") (pintype "passive"))
    )
  )
)
